# Miscellaneous_Connectors.net
KiCad netlist of a schematic drawn in Altium Designer
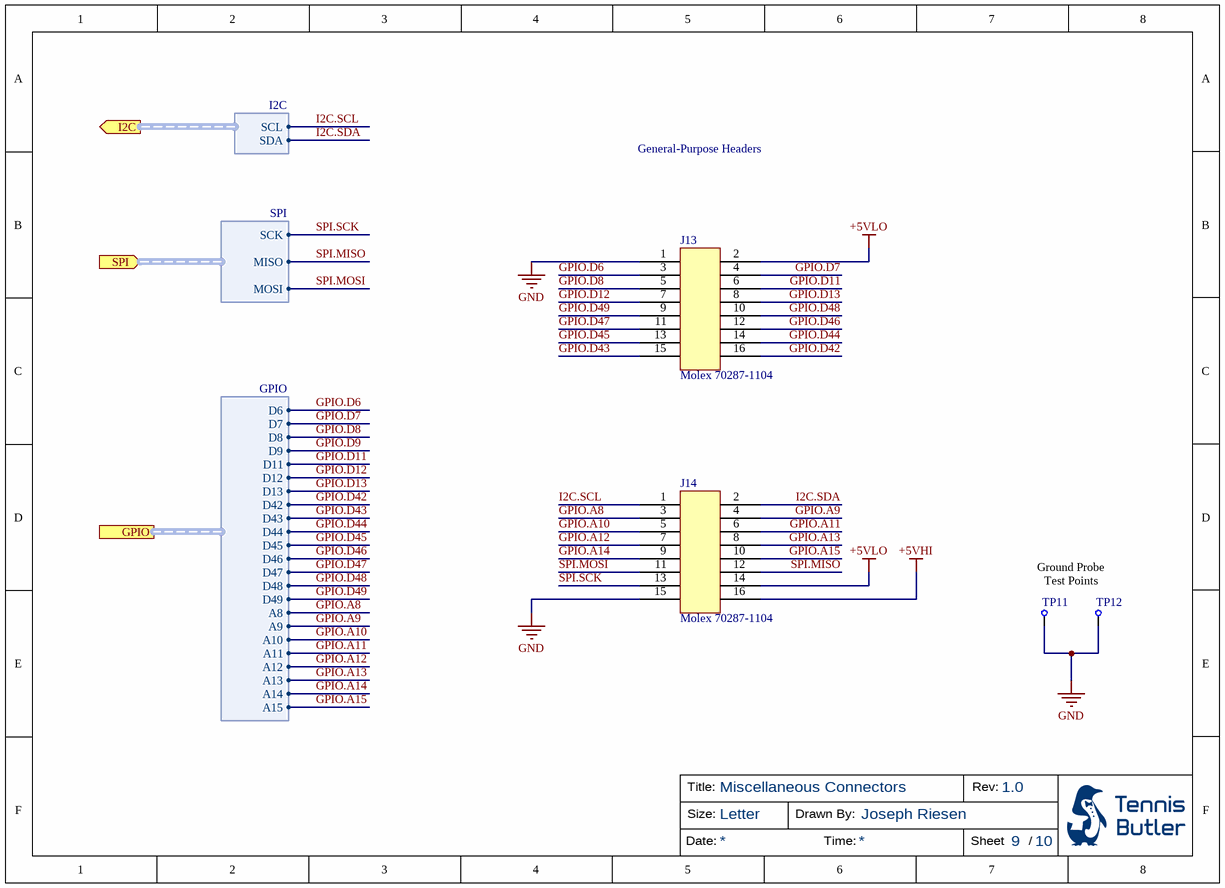
[diagram p0: Miscellaneous Connectors.SchDoc]

(export (version "E")
  (design (tool "Eeschema 10.0.6"))
  (components
    (comp (ref "J13")
      (value "Molex 70287-1104")
      (footprint "Molex 70287-1104")
      (description "CONN HEADER BKWY DL GOLD 16POS")
      (fields (field (name "MANUFACTURER") "Molex") (field (name "MANUFACTURER PART NUMBER") "0702871104"))
      (libsource (lib "TennisButler") (part "Molex 70287-1104 16-Pin (8x2) Male Header"))
    )
    (comp (ref "J14")
      (value "Molex 70287-1104")
      (footprint "Molex 70287-1104")
      (description "CONN HEADER BKWY DL GOLD 16POS")
      (fields (field (name "MANUFACTURER") "Molex") (field (name "MANUFACTURER PART NUMBER") "0702871104"))
      (libsource (lib "TennisButler") (part "Molex 70287-1104 16-Pin (8x2) Male Header"))
    )
    (comp (ref "TP11")
      (value "GND")
      (footprint "Test Point")
      (libsource (lib "Miscellaneous") (part "Test Point"))
    )
    (comp (ref "TP12")
      (value "GND")
      (footprint "Test Point")
      (libsource (lib "Miscellaneous") (part "Test Point"))
    )
  )
  (nets
    (net (code "4") (name "+5VHI") (class "Default") (node (ref "J14") (pin "16") (pintype "passive")))
    (net (code "5") (name "+5VLO") (class "Default")
      (node (ref "J13") (pin "2") (pintype "passive"))
      (node (ref "J14") (pin "14") (pintype "passive"))
    )
    (net (code "6") (name "/GPIO.A8") (class "Default") (node (ref "J14") (pin "3") (pintype "passive")))
    (net (code "7") (name "/GPIO.A9") (class "Default") (node (ref "J14") (pin "4") (pintype "passive")))
    (net (code "8") (name "/GPIO.A10") (class "Default") (node (ref "J14") (pin "5") (pintype "passive")))
    (net (code "9") (name "/GPIO.A11") (class "Default") (node (ref "J14") (pin "6") (pintype "passive")))
    (net (code "10") (name "/GPIO.A12") (class "Default") (node (ref "J14") (pin "7") (pintype "passive")))
    (net (code "11") (name "/GPIO.A13") (class "Default") (node (ref "J14") (pin "8") (pintype "passive")))
    (net (code "12") (name "/GPIO.A14") (class "Default") (node (ref "J14") (pin "9") (pintype "passive")))
    (net (code "13") (name "/GPIO.A15") (class "Default") (node (ref "J14") (pin "10") (pintype "passive")))
    (net (code "14") (name "/GPIO.D6") (class "Default") (node (ref "J13") (pin "3") (pintype "passive")))
    (net (code "15") (name "/GPIO.D7") (class "Default") (node (ref "J13") (pin "4") (pintype "passive")))
    (net (code "16") (name "/GPIO.D8") (class "Default") (node (ref "J13") (pin "5") (pintype "passive")))
    (net (code "18") (name "/GPIO.D11") (class "Default") (node (ref "J13") (pin "6") (pintype "passive")))
    (net (code "19") (name "/GPIO.D12") (class "Default") (node (ref "J13") (pin "7") (pintype "passive")))
    (net (code "20") (name "/GPIO.D13") (class "Default") (node (ref "J13") (pin "8") (pintype "passive")))
    (net (code "21") (name "/GPIO.D42") (class "Default") (node (ref "J13") (pin "16") (pintype "passive")))
    (net (code "22") (name "/GPIO.D43") (class "Default") (node (ref "J13") (pin "15") (pintype "passive")))
    (net (code "23") (name "/GPIO.D44") (class "Default") (node (ref "J13") (pin "14") (pintype "passive")))
    (net (code "24") (name "/GPIO.D45") (class "Default") (node (ref "J13") (pin "13") (pintype "passive")))
    (net (code "25") (name "/GPIO.D46") (class "Default") (node (ref "J13") (pin "12") (pintype "passive")))
    (net (code "26") (name "/GPIO.D47") (class "Default") (node (ref "J13") (pin "11") (pintype "passive")))
    (net (code "27") (name "/GPIO.D48") (class "Default") (node (ref "J13") (pin "10") (pintype "passive")))
    (net (code "28") (name "/GPIO.D49") (class "Default") (node (ref "J13") (pin "9") (pintype "passive")))
    (net (code "29") (name "/I2C.SCL") (class "Default") (node (ref "J14") (pin "1") (pintype "passive")))
    (net (code "30") (name "/I2C.SDA") (class "Default") (node (ref "J14") (pin "2") (pintype "passive")))
    (net (code "31") (name "/SPI.MISO") (class "Default") (node (ref "J14") (pin "12") (pintype "passive")))
    (net (code "32") (name "/SPI.MOSI") (class "Default") (node (ref "J14") (pin "11") (pintype "passive")))
    (net (code "33") (name "/SPI.SCK") (class "Default") (node (ref "J14") (pin "13") (pintype "passive")))
    (net (code "37") (name "GND") (class "Default")
      (node (ref "J13") (pin "1") (pintype "passive"))
      (node (ref "J14") (pin "15") (pintype "passive"))
      (node (ref "TP11") (pin "1") (pinfunction "1_1") (pintype "passive"))
      (node (ref "TP12") (pin "1") (pinfunction "1_1") (pintype "passive"))
    )
  )
)
